# Jlink_OB.net
KiCad netlist of a schematic drawn in Altium Designer
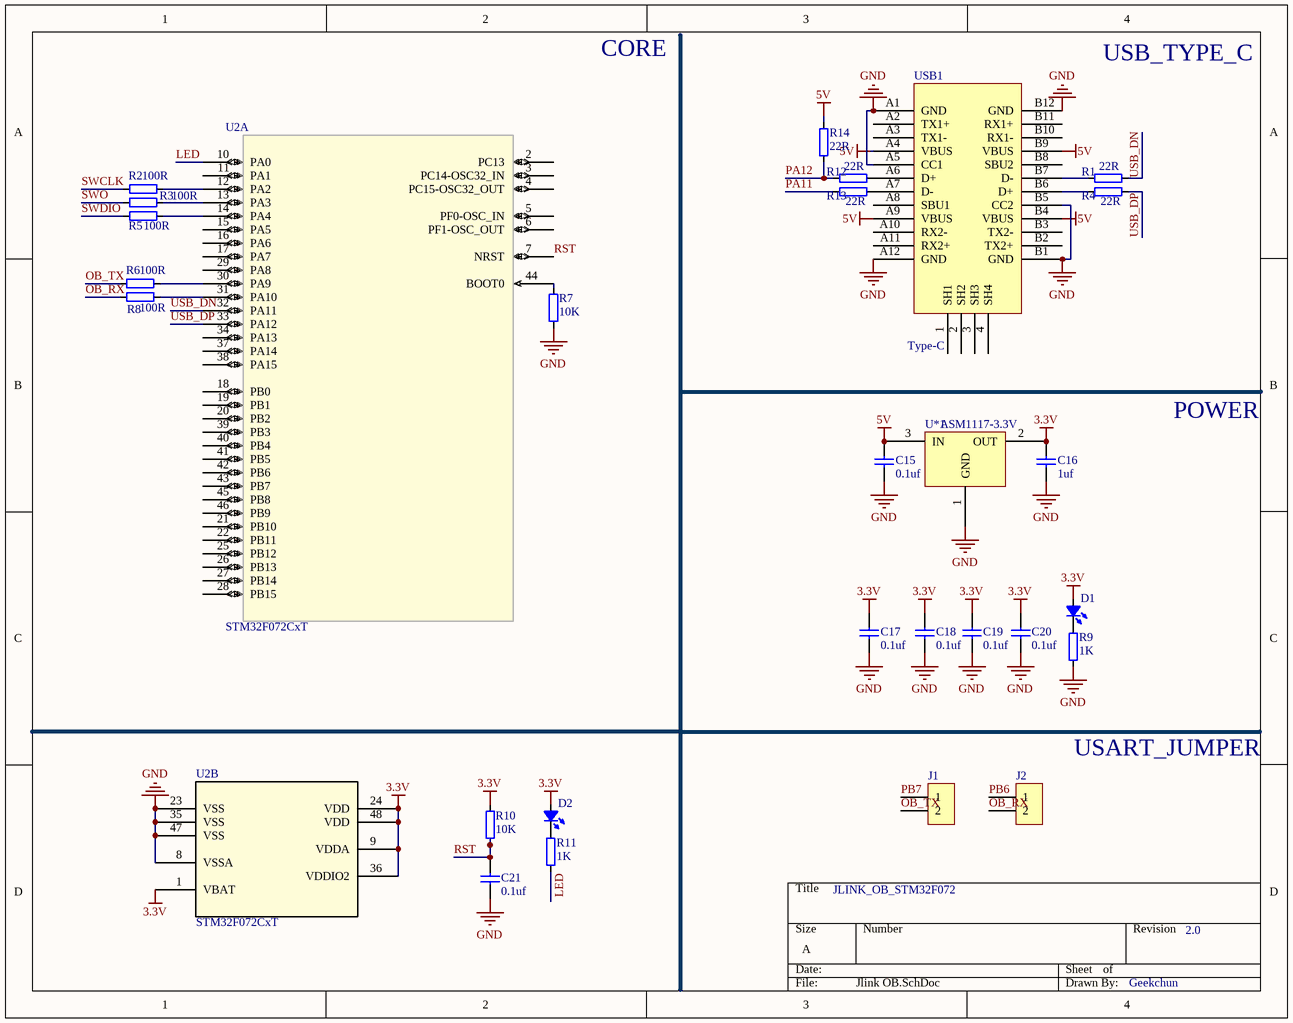
[diagram p0: Jlink OB.SchDoc]

(export (version "E")
  (design (tool "Eeschema 10.0.6"))
  (components
    (comp (ref "C15")
      (value "0.1uf")
      (footprint "C 0603_L")
      (description "Capacitor, NP0, ?.1pF")
      (fields (field (name "PART NUMBER") "C0402-1.2p") (field (name "PUBLISHER") "Nordic Semiconductor"))
      (libsource (lib "52") (part "CAP"))
    )
    (comp (ref "C16")
      (value "1uf")
      (footprint "C 0603_L")
      (description "Capacitor, NP0, ?.1pF")
      (fields (field (name "PART NUMBER") "C0402-1.2p") (field (name "PUBLISHER") "Nordic Semiconductor"))
      (libsource (lib "52") (part "CAP"))
    )
    (comp (ref "C17")
      (value "0.1uf")
      (footprint "C 0603_L")
      (description "Capacitor, NP0, ?.1pF")
      (fields (field (name "PART NUMBER") "C0402-1.2p") (field (name "PUBLISHER") "Nordic Semiconductor"))
      (libsource (lib "52") (part "CAP"))
    )
    (comp (ref "C18")
      (value "0.1uf")
      (footprint "C 0603_L")
      (description "Capacitor, NP0, ?.1pF")
      (fields (field (name "PART NUMBER") "C0402-1.2p") (field (name "PUBLISHER") "Nordic Semiconductor"))
      (libsource (lib "52") (part "CAP"))
    )
    (comp (ref "C19")
      (value "0.1uf")
      (footprint "C 0603_L")
      (description "Capacitor, NP0, ?.1pF")
      (fields (field (name "PART NUMBER") "C0402-1.2p") (field (name "PUBLISHER") "Nordic Semiconductor"))
      (libsource (lib "52") (part "CAP"))
    )
    (comp (ref "C20")
      (value "0.1uf")
      (footprint "C 0603_L")
      (description "Capacitor, NP0, ?.1pF")
      (fields (field (name "PART NUMBER") "C0402-1.2p") (field (name "PUBLISHER") "Nordic Semiconductor"))
      (libsource (lib "52") (part "CAP"))
    )
    (comp (ref "C21")
      (value "0.1uf")
      (footprint "C 0603_L")
      (description "Capacitor, NP0, ?.1pF")
      (fields (field (name "PART NUMBER") "C0402-1.2p") (field (name "PUBLISHER") "Nordic Semiconductor"))
      (libsource (lib "52") (part "CAP"))
    )
    (comp (ref "D1")
      (value "LED_0603")
      (footprint "LED 0603B")
      (description "LED")
      (libsource (lib "SCH_Active") (part "LED_0603"))
    )
    (comp (ref "D2")
      (value "LED_0603")
      (footprint "LED 0603B")
      (description "LED")
      (libsource (lib "SCH_Active") (part "LED_0603"))
    )
    (comp (ref "J1")
      (value "USART JUMPER")
      (footprint "HDR2.54-LI-2P")
      (description "Connector")
      (libsource (lib "插件") (part "CON2"))
    )
    (comp (ref "J2")
      (value "USART JUMPER")
      (footprint "HDR2.54-LI-2P")
      (description "Connector")
      (libsource (lib "插件") (part "CON2"))
    )
    (comp (ref "R1") (value "22R") (footprint "R 0603_L") (libsource (lib "电阻") (part "RES")))
    (comp (ref "R2") (value "100R") (footprint "R 0603_L") (libsource (lib "电阻") (part "RES")))
    (comp (ref "R3") (value "100R") (footprint "R 0603_L") (libsource (lib "电阻") (part "RES")))
    (comp (ref "R4") (value "22R") (footprint "R 0603_L") (libsource (lib "电阻") (part "RES")))
    (comp (ref "R5") (value "100R") (footprint "R 0603_L") (libsource (lib "电阻") (part "RES")))
    (comp (ref "R6") (value "100R") (footprint "R 0603_L") (libsource (lib "电阻") (part "RES")))
    (comp (ref "R7") (value "10K") (footprint "R 0603_L") (libsource (lib "电阻") (part "RES")))
    (comp (ref "R8") (value "100R") (footprint "R 0603_L") (libsource (lib "电阻") (part "RES")))
    (comp (ref "R9") (value "1K") (footprint "R 0603_L") (libsource (lib "电阻") (part "RES")))
    (comp (ref "R10") (value "10K") (footprint "R 0603_L") (libsource (lib "电阻") (part "RES")))
    (comp (ref "R11") (value "1K") (footprint "R 0603_L") (libsource (lib "电阻") (part "RES")))
    (comp (ref "R12") (value "22R") (footprint "R 0603_L") (libsource (lib "电阻") (part "RES")))
    (comp (ref "R13") (value "22R") (footprint "R 0603_L") (libsource (lib "电阻") (part "RES")))
    (comp (ref "R14") (value "22R") (footprint "R 0603_L") (libsource (lib "电阻") (part "RES")))
    (comp (ref "U*1")
      (value "ASM1117-3.3V")
      (footprint "SOT223_L")
      (description "三端可调或固定电压3.3V")
      (libsource (lib "STM32F103C及ASM1117") (part "ASM1117-3.3V"))
    )
    (comp (ref "U2")
      (value "STM32F072CxT")
      (footprint "LQFP48 7X7_L")
      (description "Imported")
      (fields
        (field (name "MANUFACTURER_PART_NUMBER") "stm32f072cxt")
        (field (name "COPYRIGHT") "Copyright (C) 2016 Accelerated Designs. All rights reserved")
      )
      (libsource (lib "STM32F072CB") (part "STM32F072CxT"))
    )
    (comp (ref "USB1") (value "Type-C") (footprint "usb typec") (libsource (lib "元件") (part "Type-C")))
  )
  (nets
    (net (code "1") (name "/LED") (class "Default")
      (node (ref "R11") (pin "1") (pinfunction "1_1") (pintype "passive"))
      (node (ref "U2") (pin "10") (pinfunction "PA0_10") (pintype "bidirectional"))
    )
    (net (code "2") (name "/OB_RX") (class "Default")
      (node (ref "J2") (pin "2") (pinfunction "2_2") (pintype "passive"))
      (node (ref "R8") (pin "1") (pinfunction "1_1") (pintype "passive"))
    )
    (net (code "3") (name "/OB_TX") (class "Default")
      (node (ref "J1") (pin "2") (pinfunction "2_2") (pintype "passive"))
      (node (ref "R6") (pin "1") (pinfunction "1_1") (pintype "passive"))
    )
    (net (code "4") (name "/PA11") (class "Default")
      (node (ref "R13") (pin "1") (pinfunction "1_1") (pintype "passive"))
    )
    (net (code "5") (name "/PA12") (class "Default")
      (node (ref "R12") (pin "1") (pinfunction "1_1") (pintype "passive"))
      (node (ref "R14") (pin "1") (pinfunction "1_1") (pintype "passive"))
    )
    (net (code "6") (name "/PB6") (class "Default")
      (node (ref "J2") (pin "1") (pinfunction "1_1") (pintype "passive"))
    )
    (net (code "7") (name "/PB7") (class "Default")
      (node (ref "J1") (pin "1") (pinfunction "1_1") (pintype "passive"))
    )
    (net (code "8") (name "/RST") (class "Default")
      (node (ref "C21") (pin "2") (pinfunction "2_2") (pintype "passive"))
      (node (ref "R10") (pin "1") (pinfunction "1_1") (pintype "passive"))
      (node (ref "U2") (pin "7") (pinfunction "NRST_7") (pintype "bidirectional"))
    )
    (net (code "9") (name "/SWCLK") (class "Default")
      (node (ref "R2") (pin "1") (pinfunction "1_1") (pintype "passive"))
    )
    (net (code "10") (name "/SWDIO") (class "Default")
      (node (ref "R5") (pin "1") (pinfunction "1_1") (pintype "passive"))
    )
    (net (code "11") (name "/SWO") (class "Default")
      (node (ref "R3") (pin "1") (pinfunction "1_1") (pintype "passive"))
    )
    (net (code "12") (name "/USB_DN") (class "Default")
      (node (ref "R1") (pin "2") (pinfunction "2_2") (pintype "passive"))
      (node (ref "U2") (pin "32") (pinfunction "PA11_32") (pintype "bidirectional"))
    )
    (net (code "13") (name "/USB_DP") (class "Default")
      (node (ref "R4") (pin "2") (pinfunction "2_2") (pintype "passive"))
      (node (ref "U2") (pin "33") (pinfunction "PA12_33") (pintype "bidirectional"))
    )
    (net (code "14") (name "3.3V") (class "Default")
      (node (ref "C16") (pin "2") (pinfunction "2_2") (pintype "passive"))
      (node (ref "C17") (pin "2") (pinfunction "2_2") (pintype "passive"))
      (node (ref "C18") (pin "2") (pinfunction "2_2") (pintype "passive"))
      (node (ref "C19") (pin "2") (pinfunction "2_2") (pintype "passive"))
      (node (ref "C20") (pin "2") (pinfunction "2_2") (pintype "passive"))
      (node (ref "D1") (pin "1") (pinfunction "A_1") (pintype "passive"))
      (node (ref "D2") (pin "1") (pinfunction "A_1") (pintype "passive"))
      (node (ref "R10") (pin "2") (pinfunction "2_2") (pintype "passive"))
      (node (ref "U*1") (pin "2") (pinfunction "OUT_2") (pintype "passive"))
      (node (ref "U2") (pin "1") (pinfunction "VBAT_1") (pintype "power_in"))
      (node (ref "U2") (pin "24") (pinfunction "VDD_24") (pintype "power_in"))
      (node (ref "U2") (pin "36") (pinfunction "VDDIO2_36") (pintype "power_in"))
      (node (ref "U2") (pin "48") (pinfunction "VDD_48") (pintype "power_in"))
      (node (ref "U2") (pin "9") (pinfunction "VDDA_9") (pintype "power_in"))
    )
    (net (code "15") (name "5V") (class "Default")
      (node (ref "C15") (pin "2") (pinfunction "2_2") (pintype "passive"))
      (node (ref "R14") (pin "2") (pinfunction "2_2") (pintype "passive"))
      (node (ref "U*1") (pin "3") (pinfunction "IN_3") (pintype "passive"))
      (node (ref "USB1") (pin "A4") (pinfunction "VBUS_A4") (pintype "passive"))
      (node (ref "USB1") (pin "A9") (pinfunction "VBUS_A9") (pintype "passive"))
      (node (ref "USB1") (pin "B4") (pinfunction "VBUS_B4") (pintype "passive"))
      (node (ref "USB1") (pin "B9") (pinfunction "VBUS_B9") (pintype "passive"))
    )
    (net (code "16") (name "GND") (class "Default")
      (node (ref "C15") (pin "1") (pinfunction "1_1") (pintype "passive"))
      (node (ref "C16") (pin "1") (pinfunction "1_1") (pintype "passive"))
      (node (ref "C17") (pin "1") (pinfunction "1_1") (pintype "passive"))
      (node (ref "C18") (pin "1") (pinfunction "1_1") (pintype "passive"))
      (node (ref "C19") (pin "1") (pinfunction "1_1") (pintype "passive"))
      (node (ref "C20") (pin "1") (pinfunction "1_1") (pintype "passive"))
      (node (ref "C21") (pin "1") (pinfunction "1_1") (pintype "passive"))
      (node (ref "R7") (pin "2") (pinfunction "2_2") (pintype "passive"))
      (node (ref "R9") (pin "1") (pinfunction "1_1") (pintype "passive"))
      (node (ref "U*1") (pin "1") (pinfunction "GND_1") (pintype "passive"))
      (node (ref "U2") (pin "23") (pinfunction "VSS_23") (pintype "power_in"))
      (node (ref "U2") (pin "35") (pinfunction "VSS_35") (pintype "power_in"))
      (node (ref "U2") (pin "47") (pinfunction "VSS_47") (pintype "power_in"))
      (node (ref "U2") (pin "8") (pinfunction "VSSA_8") (pintype "power_in"))
      (node (ref "USB1") (pin "A1") (pinfunction "GND_A1") (pintype "passive"))
      (node (ref "USB1") (pin "A12") (pinfunction "GND_A12") (pintype "passive"))
      (node (ref "USB1") (pin "A5") (pinfunction "CC1_A5") (pintype "passive"))
      (node (ref "USB1") (pin "B1") (pinfunction "GND_B1") (pintype "passive"))
      (node (ref "USB1") (pin "B12") (pinfunction "GND_B12") (pintype "passive"))
      (node (ref "USB1") (pin "B5") (pinfunction "CC2_B5") (pintype "passive"))
    )
    (net (code "17") (name "Net-(D1-K)") (class "Default")
      (node (ref "D1") (pin "2") (pinfunction "K_2") (pintype "passive"))
      (node (ref "R9") (pin "2") (pinfunction "2_2") (pintype "passive"))
    )
    (net (code "18") (name "Net-(D2-K)") (class "Default")
      (node (ref "D2") (pin "2") (pinfunction "K_2") (pintype "passive"))
      (node (ref "R11") (pin "2") (pinfunction "2_2") (pintype "passive"))
    )
    (net (code "19") (name "Net-(R1-Pad1)") (class "Default")
      (node (ref "R1") (pin "1") (pinfunction "1_1") (pintype "passive"))
      (node (ref "USB1") (pin "B7") (pinfunction "D-_B7") (pintype "passive"))
    )
    (net (code "20") (name "Net-(R4-Pad1)") (class "Default")
      (node (ref "R4") (pin "1") (pinfunction "1_1") (pintype "passive"))
      (node (ref "USB1") (pin "B6") (pinfunction "D+_B6") (pintype "passive"))
    )
    (net (code "21") (name "Net-(R12-Pad2)") (class "Default")
      (node (ref "R12") (pin "2") (pinfunction "2_2") (pintype "passive"))
      (node (ref "USB1") (pin "A6") (pinfunction "D+_A6") (pintype "passive"))
    )
    (net (code "22") (name "Net-(R13-Pad2)") (class "Default")
      (node (ref "R13") (pin "2") (pinfunction "2_2") (pintype "passive"))
      (node (ref "USB1") (pin "A7") (pinfunction "D-_A7") (pintype "passive"))
    )
    (net (code "23") (name "Net-(U2A-BOOT0)") (class "Default")
      (node (ref "R7") (pin "1") (pinfunction "1_1") (pintype "passive"))
      (node (ref "U2") (pin "44") (pinfunction "BOOT0_44") (pintype "input"))
    )
    (net (code "24") (name "Net-(U2A-PA2)") (class "Default")
      (node (ref "R2") (pin "2") (pinfunction "2_2") (pintype "passive"))
      (node (ref "U2") (pin "12") (pinfunction "PA2_12") (pintype "bidirectional"))
    )
    (net (code "25") (name "Net-(U2A-PA3)") (class "Default")
      (node (ref "R3") (pin "2") (pinfunction "2_2") (pintype "passive"))
      (node (ref "U2") (pin "13") (pinfunction "PA3_13") (pintype "bidirectional"))
    )
    (net (code "26") (name "Net-(U2A-PA4)") (class "Default")
      (node (ref "R5") (pin "2") (pinfunction "2_2") (pintype "passive"))
      (node (ref "U2") (pin "14") (pinfunction "PA4_14") (pintype "bidirectional"))
    )
    (net (code "27") (name "Net-(U2A-PA9)") (class "Default")
      (node (ref "R6") (pin "2") (pinfunction "2_2") (pintype "passive"))
      (node (ref "U2") (pin "30") (pinfunction "PA9_30") (pintype "bidirectional"))
    )
    (net (code "28") (name "Net-(U2A-PA10)") (class "Default")
      (node (ref "R8") (pin "2") (pinfunction "2_2") (pintype "passive"))
      (node (ref "U2") (pin "31") (pinfunction "PA10_31") (pintype "bidirectional"))
    )
    (net (code "29") (name "unconnected-(U2A-PA1-Pad11)") (class "Default")
      (node (ref "U2") (pin "11") (pinfunction "PA1_11") (pintype "bidirectional"))
    )
    (net (code "30") (name "unconnected-(U2A-PA5-Pad15)") (class "Default")
      (node (ref "U2") (pin "15") (pinfunction "PA5_15") (pintype "bidirectional"))
    )
    (net (code "31") (name "unconnected-(U2A-PA6-Pad16)") (class "Default")
      (node (ref "U2") (pin "16") (pinfunction "PA6_16") (pintype "bidirectional"))
    )
    (net (code "32") (name "unconnected-(U2A-PA7-Pad17)") (class "Default")
      (node (ref "U2") (pin "17") (pinfunction "PA7_17") (pintype "bidirectional"))
    )
    (net (code "33") (name "unconnected-(U2A-PA8-Pad29)") (class "Default")
      (node (ref "U2") (pin "29") (pinfunction "PA8_29") (pintype "bidirectional"))
    )
    (net (code "34") (name "unconnected-(U2A-PA13-Pad34)") (class "Default")
      (node (ref "U2") (pin "34") (pinfunction "PA13_34") (pintype "bidirectional"))
    )
    (net (code "35") (name "unconnected-(U2A-PA14-Pad37)") (class "Default")
      (node (ref "U2") (pin "37") (pinfunction "PA14_37") (pintype "bidirectional"))
    )
    (net (code "36") (name "unconnected-(U2A-PA15-Pad38)") (class "Default")
      (node (ref "U2") (pin "38") (pinfunction "PA15_38") (pintype "bidirectional"))
    )
    (net (code "37") (name "unconnected-(U2A-PB0-Pad18)") (class "Default")
      (node (ref "U2") (pin "18") (pinfunction "PB0_18") (pintype "bidirectional"))
    )
    (net (code "38") (name "unconnected-(U2A-PB1-Pad19)") (class "Default")
      (node (ref "U2") (pin "19") (pinfunction "PB1_19") (pintype "bidirectional"))
    )
    (net (code "39") (name "unconnected-(U2A-PB2-Pad20)") (class "Default")
      (node (ref "U2") (pin "20") (pinfunction "PB2_20") (pintype "bidirectional"))
    )
    (net (code "40") (name "unconnected-(U2A-PB3-Pad39)") (class "Default")
      (node (ref "U2") (pin "39") (pinfunction "PB3_39") (pintype "bidirectional"))
    )
    (net (code "41") (name "unconnected-(U2A-PB4-Pad40)") (class "Default")
      (node (ref "U2") (pin "40") (pinfunction "PB4_40") (pintype "bidirectional"))
    )
    (net (code "42") (name "unconnected-(U2A-PB5-Pad41)") (class "Default")
      (node (ref "U2") (pin "41") (pinfunction "PB5_41") (pintype "bidirectional"))
    )
    (net (code "43") (name "unconnected-(U2A-PB6-Pad42)") (class "Default")
      (node (ref "U2") (pin "42") (pinfunction "PB6_42") (pintype "bidirectional"))
    )
    (net (code "44") (name "unconnected-(U2A-PB7-Pad43)") (class "Default")
      (node (ref "U2") (pin "43") (pinfunction "PB7_43") (pintype "bidirectional"))
    )
    (net (code "45") (name "unconnected-(U2A-PB8-Pad45)") (class "Default")
      (node (ref "U2") (pin "45") (pinfunction "PB8_45") (pintype "bidirectional"))
    )
    (net (code "46") (name "unconnected-(U2A-PB9-Pad46)") (class "Default")
      (node (ref "U2") (pin "46") (pinfunction "PB9_46") (pintype "bidirectional"))
    )
    (net (code "47") (name "unconnected-(U2A-PB10-Pad21)") (class "Default")
      (node (ref "U2") (pin "21") (pinfunction "PB10_21") (pintype "bidirectional"))
    )
    (net (code "48") (name "unconnected-(U2A-PB11-Pad22)") (class "Default")
      (node (ref "U2") (pin "22") (pinfunction "PB11_22") (pintype "bidirectional"))
    )
    (net (code "49") (name "unconnected-(U2A-PB12-Pad25)") (class "Default")
      (node (ref "U2") (pin "25") (pinfunction "PB12_25") (pintype "bidirectional"))
    )
    (net (code "50") (name "unconnected-(U2A-PB13-Pad26)") (class "Default")
      (node (ref "U2") (pin "26") (pinfunction "PB13_26") (pintype "bidirectional"))
    )
    (net (code "51") (name "unconnected-(U2A-PB14-Pad27)") (class "Default")
      (node (ref "U2") (pin "27") (pinfunction "PB14_27") (pintype "bidirectional"))
    )
    (net (code "52") (name "unconnected-(U2A-PB15-Pad28)") (class "Default")
      (node (ref "U2") (pin "28") (pinfunction "PB15_28") (pintype "bidirectional"))
    )
    (net (code "53") (name "unconnected-(U2A-PC13-Pad2)") (class "Default")
      (node (ref "U2") (pin "2") (pinfunction "PC13_2") (pintype "bidirectional"))
    )
    (net (code "54") (name "unconnected-(U2A-PC14-OSC32_IN-Pad3)") (class "Default")
      (node (ref "U2") (pin "3") (pinfunction "PC14-OSC32_IN_3") (pintype "bidirectional"))
    )
    (net (code "55") (name "unconnected-(U2A-PC15-OSC32_OUT-Pad4)") (class "Default")
      (node (ref "U2") (pin "4") (pinfunction "PC15-OSC32_OUT_4") (pintype "bidirectional"))
    )
    (net (code "56") (name "unconnected-(U2A-PF0-OSC_IN-Pad5)") (class "Default")
      (node (ref "U2") (pin "5") (pinfunction "PF0-OSC_IN_5") (pintype "bidirectional"))
    )
    (net (code "57") (name "unconnected-(U2A-PF1-OSC_OUT-Pad6)") (class "Default")
      (node (ref "U2") (pin "6") (pinfunction "PF1-OSC_OUT_6") (pintype "bidirectional"))
    )
    (net (code "58") (name "unconnected-(USB1-RX1+-PadB11)") (class "Default")
      (node (ref "USB1") (pin "B11") (pinfunction "RX1+_B11") (pintype "passive"))
    )
    (net (code "59") (name "unconnected-(USB1-RX1--PadB10)") (class "Default")
      (node (ref "USB1") (pin "B10") (pinfunction "RX1-_B10") (pintype "passive"))
    )
    (net (code "60") (name "unconnected-(USB1-RX2+-PadA11)") (class "Default")
      (node (ref "USB1") (pin "A11") (pinfunction "RX2+_A11") (pintype "passive"))
    )
    (net (code "61") (name "unconnected-(USB1-RX2--PadA10)") (class "Default")
      (node (ref "USB1") (pin "A10") (pinfunction "RX2-_A10") (pintype "passive"))
    )
    (net (code "62") (name "unconnected-(USB1-SBU1-PadA8)") (class "Default")
      (node (ref "USB1") (pin "A8") (pinfunction "SBU1_A8") (pintype "passive"))
    )
    (net (code "63") (name "unconnected-(USB1-SBU2-PadB8)") (class "Default")
      (node (ref "USB1") (pin "B8") (pinfunction "SBU2_B8") (pintype "passive"))
    )
    (net (code "64") (name "unconnected-(USB1-SH1-Pad1)") (class "Default")
      (node (ref "USB1") (pin "1") (pinfunction "SH1_1") (pintype "passive"))
    )
    (net (code "65") (name "unconnected-(USB1-SH2-Pad2)") (class "Default")
      (node (ref "USB1") (pin "2") (pinfunction "SH2_2") (pintype "passive"))
    )
    (net (code "66") (name "unconnected-(USB1-SH3-Pad3)") (class "Default")
      (node (ref "USB1") (pin "3") (pinfunction "SH3_3") (pintype "passive"))
    )
    (net (code "67") (name "unconnected-(USB1-SH4-Pad4)") (class "Default")
      (node (ref "USB1") (pin "4") (pinfunction "SH4_4") (pintype "passive"))
    )
    (net (code "68") (name "unconnected-(USB1-TX1+-PadA2)") (class "Default")
      (node (ref "USB1") (pin "A2") (pinfunction "TX1+_A2") (pintype "passive"))
    )
    (net (code "69") (name "unconnected-(USB1-TX1--PadA3)") (class "Default")
      (node (ref "USB1") (pin "A3") (pinfunction "TX1-_A3") (pintype "passive"))
    )
    (net (code "70") (name "unconnected-(USB1-TX2+-PadB2)") (class "Default")
      (node (ref "USB1") (pin "B2") (pinfunction "TX2+_B2") (pintype "passive"))
    )
    (net (code "71") (name "unconnected-(USB1-TX2--PadB3)") (class "Default")
      (node (ref "USB1") (pin "B3") (pinfunction "TX2-_B3") (pintype "passive"))
    )
  )
)
